# Power.net
KiCad netlist of a schematic drawn in Altium Designer
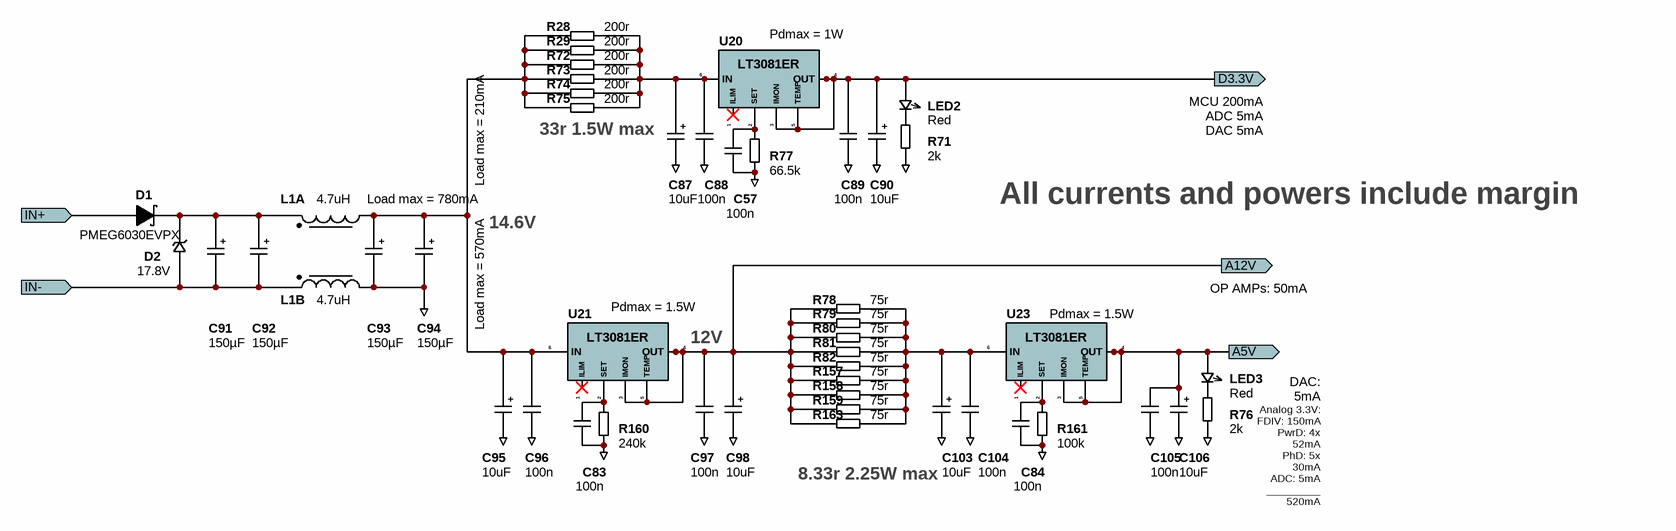
[diagram p0: Power.SchDoc]

(export (version "E")
  (design (tool "Eeschema 10.0.6"))
  (components
    (comp (ref "C57")
      (value "100n")
      (footprint "0402-Capacitor")
      (description "Capacitor 0402")
      (fields (field (name "TOLERANCE") "±20%"))
      (libsource (lib "PRL_PDC") (part "C_0402"))
    )
    (comp (ref "C83")
      (value "100n")
      (footprint "0402-Capacitor")
      (description "Capacitor 0402")
      (fields (field (name "TOLERANCE") "±20%"))
      (libsource (lib "PRL_PDC") (part "C_0402"))
    )
    (comp (ref "C84")
      (value "100n")
      (footprint "0402-Capacitor")
      (description "Capacitor 0402")
      (fields (field (name "TOLERANCE") "±20%"))
      (libsource (lib "PRL_PDC") (part "C_0402"))
    )
    (comp (ref "C87")
      (value "10uF")
      (footprint "2312-6032 Tantalum Capacitor")
      (description "CAP TANT 10UF 10% 25V 2312")
      (libsource (lib "PRL_PDC") (part "C_10uF_Tant_25V_2312"))
    )
    (comp (ref "C88")
      (value "100n")
      (footprint "0402-Capacitor")
      (description "Capacitor 0402")
      (fields (field (name "TOLERANCE") "±20%"))
      (libsource (lib "PRL_PDC") (part "C_0402"))
    )
    (comp (ref "C89")
      (value "100n")
      (footprint "0402-Capacitor")
      (description "Capacitor 0402")
      (fields (field (name "TOLERANCE") "±20%"))
      (libsource (lib "PRL_PDC") (part "C_0402"))
    )
    (comp (ref "C90")
      (value "10uF")
      (footprint "2312-6032 Tantalum Capacitor")
      (description "CAP TANT 10UF 10% 25V 2312")
      (libsource (lib "PRL_PDC") (part "C_10uF_Tant_25V_2312"))
    )
    (comp (ref "C91")
      (value "150µF")
      (footprint "2917-7343  Tantalum Capacitor")
      (description "150µF Molded Tantalum Capacitors 20V 2917")
      (fields (field (name "TOLERANCE") "±10%"))
      (libsource (lib "PRL_PDC") (part "T491X157K020AT"))
    )
    (comp (ref "C92")
      (value "150µF")
      (footprint "2917-7343  Tantalum Capacitor")
      (description "150µF Molded Tantalum Capacitors 20V 2917")
      (fields (field (name "TOLERANCE") "±10%"))
      (libsource (lib "PRL_PDC") (part "T491X157K020AT"))
    )
    (comp (ref "C93")
      (value "150µF")
      (footprint "2917-7343  Tantalum Capacitor")
      (description "150µF Molded Tantalum Capacitors 20V 2917")
      (fields (field (name "TOLERANCE") "±10%"))
      (libsource (lib "PRL_PDC") (part "T491X157K020AT"))
    )
    (comp (ref "C94")
      (value "150µF")
      (footprint "2917-7343  Tantalum Capacitor")
      (description "150µF Molded Tantalum Capacitors 20V 2917")
      (fields (field (name "TOLERANCE") "±10%"))
      (libsource (lib "PRL_PDC") (part "T491X157K020AT"))
    )
    (comp (ref "C95")
      (value "10uF")
      (footprint "2312-6032 Tantalum Capacitor")
      (description "CAP TANT 10UF 10% 25V 2312")
      (libsource (lib "PRL_PDC") (part "C_10uF_Tant_25V_2312"))
    )
    (comp (ref "C96")
      (value "100n")
      (footprint "0402-Capacitor")
      (description "Capacitor 0402")
      (fields (field (name "TOLERANCE") "±20%"))
      (libsource (lib "PRL_PDC") (part "C_0402"))
    )
    (comp (ref "C97")
      (value "100n")
      (footprint "0402-Capacitor")
      (description "Capacitor 0402")
      (fields (field (name "TOLERANCE") "±20%"))
      (libsource (lib "PRL_PDC") (part "C_0402"))
    )
    (comp (ref "C98")
      (value "10uF")
      (footprint "2312-6032 Tantalum Capacitor")
      (description "CAP TANT 10UF 10% 25V 2312")
      (libsource (lib "PRL_PDC") (part "C_10uF_Tant_25V_2312"))
    )
    (comp (ref "C103")
      (value "10uF")
      (footprint "2312-6032 Tantalum Capacitor")
      (description "CAP TANT 10UF 10% 25V 2312")
      (libsource (lib "PRL_PDC") (part "C_10uF_Tant_25V_2312"))
    )
    (comp (ref "C104")
      (value "100n")
      (footprint "0402-Capacitor")
      (description "Capacitor 0402")
      (fields (field (name "TOLERANCE") "±20%"))
      (libsource (lib "PRL_PDC") (part "C_0402"))
    )
    (comp (ref "C105")
      (value "100n")
      (footprint "0402-Capacitor")
      (description "Capacitor 0402")
      (fields (field (name "TOLERANCE") "±20%"))
      (libsource (lib "PRL_PDC") (part "C_0402"))
    )
    (comp (ref "C106")
      (value "10uF")
      (footprint "2312-6032 Tantalum Capacitor")
      (description "CAP TANT 10UF 10% 25V 2312")
      (libsource (lib "PRL_PDC") (part "C_10uF_Tant_25V_2312"))
    )
    (comp (ref "D1")
      (value "PMEG6030EVPX")
      (footprint "SOD128")
      (description "Diode Schottky 60V 3A Surface Mount SOD-128/CFP5")
      (fields (field (name "MANUFACTURER") "Nexperia USA Inc."))
      (libsource (lib "PRL_PDC") (part "PMEG6030EVPX"))
    )
    (comp (ref "D2")
      (value "17.8V")
      (footprint "DO-219AB")
      (description "26V Clamp 7.7A Ipp Tvs Diode Surface Mount SMF")
      (libsource (lib "PRL_PDC") (part "SMF16A-E3-08"))
    )
    (comp (ref "L1")
      (value "4.7uH")
      (footprint "PRL_PDC:LPD5030")
      (description "Shielded Coupled Inductor")
      (fields (field (name "TOLERANCE") "20%"))
      (libsource (lib "PRL_PDC") (part "LPD5030"))
    )
    (comp (ref "LED2") (value "Red") (footprint "LED0603") (libsource (lib "PRL_PDC") (part "LED0603")))
    (comp (ref "LED3") (value "Red") (footprint "LED0603") (libsource (lib "PRL_PDC") (part "LED0603")))
    (comp (ref "R28")
      (value "200r")
      (footprint "1210-Resistor")
      (description "Resistor 1210")
      (fields (field (name "TOLERANCE") "±1%"))
      (libsource (lib "PRL_PDC") (part "R_1210"))
    )
    (comp (ref "R29")
      (value "200r")
      (footprint "1210-Resistor")
      (description "Resistor 1210")
      (fields (field (name "TOLERANCE") "±1%"))
      (libsource (lib "PRL_PDC") (part "R_1210"))
    )
    (comp (ref "R71")
      (value "2k")
      (footprint "0402-RESISTOR")
      (description "Resistor 0402")
      (fields (field (name "TOLERANCE") "±1%"))
      (libsource (lib "PRL_PDC") (part "R_0402"))
    )
    (comp (ref "R72")
      (value "200r")
      (footprint "1210-Resistor")
      (description "Resistor 1210")
      (fields (field (name "TOLERANCE") "±1%"))
      (libsource (lib "PRL_PDC") (part "R_1210"))
    )
    (comp (ref "R73")
      (value "200r")
      (footprint "1210-Resistor")
      (description "Resistor 1210")
      (fields (field (name "TOLERANCE") "±1%"))
      (libsource (lib "PRL_PDC") (part "R_1210"))
    )
    (comp (ref "R74")
      (value "200r")
      (footprint "1210-Resistor")
      (description "Resistor 1210")
      (fields (field (name "TOLERANCE") "±1%"))
      (libsource (lib "PRL_PDC") (part "R_1210"))
    )
    (comp (ref "R75")
      (value "200r")
      (footprint "1210-Resistor")
      (description "Resistor 1210")
      (fields (field (name "TOLERANCE") "±1%"))
      (libsource (lib "PRL_PDC") (part "R_1210"))
    )
    (comp (ref "R76")
      (value "2k")
      (footprint "0402-RESISTOR")
      (description "Resistor 0402")
      (fields (field (name "TOLERANCE") "±1%"))
      (libsource (lib "PRL_PDC") (part "R_0402"))
    )
    (comp (ref "R77")
      (value "66.5k")
      (footprint "0805-Resistor")
      (description "Resistor 0805")
      (fields (field (name "TOLERANCE") "±1%"))
      (libsource (lib "PRL_PDC") (part "R_0805"))
    )
    (comp (ref "R78")
      (value "75r")
      (footprint "1210-Resistor")
      (description "Resistor 1210")
      (fields (field (name "TOLERANCE") "±1%"))
      (libsource (lib "PRL_PDC") (part "R_1210"))
    )
    (comp (ref "R79")
      (value "75r")
      (footprint "1210-Resistor")
      (description "Resistor 1210")
      (fields (field (name "TOLERANCE") "±1%"))
      (libsource (lib "PRL_PDC") (part "R_1210"))
    )
    (comp (ref "R80")
      (value "75r")
      (footprint "1210-Resistor")
      (description "Resistor 1210")
      (fields (field (name "TOLERANCE") "±1%"))
      (libsource (lib "PRL_PDC") (part "R_1210"))
    )
    (comp (ref "R81")
      (value "75r")
      (footprint "1210-Resistor")
      (description "Resistor 1210")
      (fields (field (name "TOLERANCE") "±1%"))
      (libsource (lib "PRL_PDC") (part "R_1210"))
    )
    (comp (ref "R82")
      (value "75r")
      (footprint "1210-Resistor")
      (description "Resistor 1210")
      (fields (field (name "TOLERANCE") "±1%"))
      (libsource (lib "PRL_PDC") (part "R_1210"))
    )
    (comp (ref "R157")
      (value "75r")
      (footprint "1210-Resistor")
      (description "Resistor 1210")
      (fields (field (name "TOLERANCE") "±1%"))
      (libsource (lib "PRL_PDC") (part "R_1210"))
    )
    (comp (ref "R158")
      (value "75r")
      (footprint "1210-Resistor")
      (description "Resistor 1210")
      (fields (field (name "TOLERANCE") "±1%"))
      (libsource (lib "PRL_PDC") (part "R_1210"))
    )
    (comp (ref "R159")
      (value "75r")
      (footprint "1210-Resistor")
      (description "Resistor 1210")
      (fields (field (name "TOLERANCE") "±1%"))
      (libsource (lib "PRL_PDC") (part "R_1210"))
    )
    (comp (ref "R160")
      (value "240k")
      (footprint "0805-Resistor")
      (description "Resistor 0805")
      (fields (field (name "TOLERANCE") "±1%"))
      (libsource (lib "PRL_PDC") (part "R_0805"))
    )
    (comp (ref "R161")
      (value "100k")
      (footprint "0805-Resistor")
      (description "Resistor 0805")
      (fields (field (name "TOLERANCE") "±1%"))
      (libsource (lib "PRL_PDC") (part "R_0805"))
    )
    (comp (ref "R163")
      (value "75r")
      (footprint "1210-Resistor")
      (description "Resistor 1210")
      (fields (field (name "TOLERANCE") "±1%"))
      (libsource (lib "PRL_PDC") (part "R_1210"))
    )
    (comp (ref "U20")
      (value "ADJ")
      (footprint "D2PAK7")
      (description "1.5A Single Resistor\r\nRugged Linear Regulator\r\nwith Monitors")
      (libsource (lib "PRL_PDC") (part "LT3081ER"))
    )
    (comp (ref "U21")
      (value "ADJ")
      (footprint "D2PAK7")
      (description "1.5A Single Resistor\r\nRugged Linear Regulator\r\nwith Monitors")
      (libsource (lib "PRL_PDC") (part "LT3081ER"))
    )
    (comp (ref "U23")
      (value "ADJ")
      (footprint "D2PAK7")
      (description "1.5A Single Resistor\r\nRugged Linear Regulator\r\nwith Monitors")
      (libsource (lib "PRL_PDC") (part "LT3081ER"))
    )
  )
  (nets
    (net (code "1") (name "/A5V") (class "Default")
      (node (ref "C105") (pin "2") (pinfunction "2_2") (pintype "passive"))
      (node (ref "C106") (pin "+") (pinfunction "+_+") (pintype "passive"))
      (node (ref "LED3") (pin "A") (pinfunction "A_A") (pintype "passive"))
      (node (ref "U23") (pin "3") (pinfunction "IMON_3") (pintype "passive"))
      (node (ref "U23") (pin "4") (pinfunction "OUT_4") (pintype "passive"))
      (node (ref "U23") (pin "5") (pinfunction "TEMP_5") (pintype "passive"))
      (node (ref "U23") (pin "EP") (pinfunction "OUT_EP") (pintype "passive"))
    )
    (net (code "2") (name "/A12V") (class "Default")
      (node (ref "C97") (pin "2") (pinfunction "2_2") (pintype "passive"))
      (node (ref "C98") (pin "+") (pinfunction "+_+") (pintype "passive"))
      (node (ref "R157") (pin "1") (pinfunction "1_1") (pintype "passive"))
      (node (ref "R158") (pin "1") (pinfunction "1_1") (pintype "passive"))
      (node (ref "R159") (pin "1") (pinfunction "1_1") (pintype "passive"))
      (node (ref "R163") (pin "1") (pinfunction "1_1") (pintype "passive"))
      (node (ref "R78") (pin "1") (pinfunction "1_1") (pintype "passive"))
      (node (ref "R79") (pin "1") (pinfunction "1_1") (pintype "passive"))
      (node (ref "R80") (pin "1") (pinfunction "1_1") (pintype "passive"))
      (node (ref "R81") (pin "1") (pinfunction "1_1") (pintype "passive"))
      (node (ref "R82") (pin "1") (pinfunction "1_1") (pintype "passive"))
      (node (ref "U21") (pin "3") (pinfunction "IMON_3") (pintype "passive"))
      (node (ref "U21") (pin "4") (pinfunction "OUT_4") (pintype "passive"))
      (node (ref "U21") (pin "5") (pinfunction "TEMP_5") (pintype "passive"))
      (node (ref "U21") (pin "EP") (pinfunction "OUT_EP") (pintype "passive"))
    )
    (net (code "3") (name "/D3.3V") (class "Default")
      (node (ref "C89") (pin "2") (pinfunction "2_2") (pintype "passive"))
      (node (ref "C90") (pin "+") (pinfunction "+_+") (pintype "passive"))
      (node (ref "LED2") (pin "A") (pinfunction "A_A") (pintype "passive"))
      (node (ref "U20") (pin "3") (pinfunction "IMON_3") (pintype "passive"))
      (node (ref "U20") (pin "4") (pinfunction "OUT_4") (pintype "passive"))
      (node (ref "U20") (pin "5") (pinfunction "TEMP_5") (pintype "passive"))
      (node (ref "U20") (pin "EP") (pinfunction "OUT_EP") (pintype "passive"))
    )
    (net (code "4") (name "/IN+") (class "Default")
      (node (ref "D1") (pin "1") (pinfunction "A_1") (pintype "passive"))
    )
    (net (code "5") (name "/IN-") (class "Default")
      (node (ref "C91") (pin "-") (pinfunction "-_-") (pintype "passive"))
      (node (ref "C92") (pin "-") (pinfunction "-_-") (pintype "passive"))
      (node (ref "D2") (pin "A") (pinfunction "A_A") (pintype "passive"))
      (node (ref "L1") (pin "4") (pinfunction "4_4") (pintype "passive"))
    )
    (net (code "6") (name "GND") (class "Default")
      (node (ref "C103") (pin "-") (pinfunction "-_-") (pintype "passive"))
      (node (ref "C104") (pin "1") (pinfunction "1_1") (pintype "passive"))
      (node (ref "C105") (pin "1") (pinfunction "1_1") (pintype "passive"))
      (node (ref "C106") (pin "-") (pinfunction "-_-") (pintype "passive"))
      (node (ref "C57") (pin "1") (pinfunction "1_1") (pintype "passive"))
      (node (ref "C83") (pin "1") (pinfunction "1_1") (pintype "passive"))
      (node (ref "C84") (pin "1") (pinfunction "1_1") (pintype "passive"))
      (node (ref "C87") (pin "-") (pinfunction "-_-") (pintype "passive"))
      (node (ref "C88") (pin "1") (pinfunction "1_1") (pintype "passive"))
      (node (ref "C89") (pin "1") (pinfunction "1_1") (pintype "passive"))
      (node (ref "C90") (pin "-") (pinfunction "-_-") (pintype "passive"))
      (node (ref "C93") (pin "-") (pinfunction "-_-") (pintype "passive"))
      (node (ref "C94") (pin "-") (pinfunction "-_-") (pintype "passive"))
      (node (ref "C95") (pin "-") (pinfunction "-_-") (pintype "passive"))
      (node (ref "C96") (pin "1") (pinfunction "1_1") (pintype "passive"))
      (node (ref "C97") (pin "1") (pinfunction "1_1") (pintype "passive"))
      (node (ref "C98") (pin "-") (pinfunction "-_-") (pintype "passive"))
      (node (ref "L1") (pin "3") (pinfunction "3_3") (pintype "passive"))
      (node (ref "R160") (pin "1") (pinfunction "1_1") (pintype "passive"))
      (node (ref "R161") (pin "1") (pinfunction "1_1") (pintype "passive"))
      (node (ref "R71") (pin "1") (pinfunction "1_1") (pintype "passive"))
      (node (ref "R76") (pin "1") (pinfunction "1_1") (pintype "passive"))
      (node (ref "R77") (pin "1") (pinfunction "1_1") (pintype "passive"))
    )
    (net (code "7") (name "Net-(D1-K)") (class "Default")
      (node (ref "C91") (pin "+") (pinfunction "+_+") (pintype "passive"))
      (node (ref "C92") (pin "+") (pinfunction "+_+") (pintype "passive"))
      (node (ref "D1") (pin "2") (pinfunction "K_2") (pintype "passive"))
      (node (ref "D2") (pin "K") (pinfunction "K_K") (pintype "passive"))
      (node (ref "L1") (pin "1") (pinfunction "1_1") (pintype "passive"))
    )
    (net (code "8") (name "Net-(LED2-PadK)") (class "Default")
      (node (ref "LED2") (pin "K") (pinfunction "K_K") (pintype "passive"))
      (node (ref "R71") (pin "2") (pinfunction "2_2") (pintype "passive"))
    )
    (net (code "9") (name "Net-(LED3-PadK)") (class "Default")
      (node (ref "LED3") (pin "K") (pinfunction "K_K") (pintype "passive"))
      (node (ref "R76") (pin "2") (pinfunction "2_2") (pintype "passive"))
    )
    (net (code "10") (name "Net-(U20-IN)") (class "Default")
      (node (ref "C87") (pin "+") (pinfunction "+_+") (pintype "passive"))
      (node (ref "C88") (pin "2") (pinfunction "2_2") (pintype "passive"))
      (node (ref "R28") (pin "2") (pinfunction "2_2") (pintype "passive"))
      (node (ref "R29") (pin "2") (pinfunction "2_2") (pintype "passive"))
      (node (ref "R72") (pin "2") (pinfunction "2_2") (pintype "passive"))
      (node (ref "R73") (pin "2") (pinfunction "2_2") (pintype "passive"))
      (node (ref "R74") (pin "2") (pinfunction "2_2") (pintype "passive"))
      (node (ref "R75") (pin "2") (pinfunction "2_2") (pintype "passive"))
      (node (ref "U20") (pin "6") (pinfunction "IN_6") (pintype "passive"))
    )
    (net (code "11") (name "Net-(U20-SET)") (class "Default")
      (node (ref "C57") (pin "2") (pinfunction "2_2") (pintype "passive"))
      (node (ref "R77") (pin "2") (pinfunction "2_2") (pintype "passive"))
      (node (ref "U20") (pin "2") (pinfunction "SET_2") (pintype "passive"))
    )
    (net (code "12") (name "Net-(U21-IN)") (class "Default")
      (node (ref "C93") (pin "+") (pinfunction "+_+") (pintype "passive"))
      (node (ref "C94") (pin "+") (pinfunction "+_+") (pintype "passive"))
      (node (ref "C95") (pin "+") (pinfunction "+_+") (pintype "passive"))
      (node (ref "C96") (pin "2") (pinfunction "2_2") (pintype "passive"))
      (node (ref "L1") (pin "2") (pinfunction "2_2") (pintype "passive"))
      (node (ref "R28") (pin "1") (pinfunction "1_1") (pintype "passive"))
      (node (ref "R29") (pin "1") (pinfunction "1_1") (pintype "passive"))
      (node (ref "R72") (pin "1") (pinfunction "1_1") (pintype "passive"))
      (node (ref "R73") (pin "1") (pinfunction "1_1") (pintype "passive"))
      (node (ref "R74") (pin "1") (pinfunction "1_1") (pintype "passive"))
      (node (ref "R75") (pin "1") (pinfunction "1_1") (pintype "passive"))
      (node (ref "U21") (pin "6") (pinfunction "IN_6") (pintype "passive"))
    )
    (net (code "13") (name "Net-(U21-SET)") (class "Default")
      (node (ref "C83") (pin "2") (pinfunction "2_2") (pintype "passive"))
      (node (ref "R160") (pin "2") (pinfunction "2_2") (pintype "passive"))
      (node (ref "U21") (pin "2") (pinfunction "SET_2") (pintype "passive"))
    )
    (net (code "14") (name "Net-(U23-IN)") (class "Default")
      (node (ref "C103") (pin "+") (pinfunction "+_+") (pintype "passive"))
      (node (ref "C104") (pin "2") (pinfunction "2_2") (pintype "passive"))
      (node (ref "R157") (pin "2") (pinfunction "2_2") (pintype "passive"))
      (node (ref "R158") (pin "2") (pinfunction "2_2") (pintype "passive"))
      (node (ref "R159") (pin "2") (pinfunction "2_2") (pintype "passive"))
      (node (ref "R163") (pin "2") (pinfunction "2_2") (pintype "passive"))
      (node (ref "R78") (pin "2") (pinfunction "2_2") (pintype "passive"))
      (node (ref "R79") (pin "2") (pinfunction "2_2") (pintype "passive"))
      (node (ref "R80") (pin "2") (pinfunction "2_2") (pintype "passive"))
      (node (ref "R81") (pin "2") (pinfunction "2_2") (pintype "passive"))
      (node (ref "R82") (pin "2") (pinfunction "2_2") (pintype "passive"))
      (node (ref "U23") (pin "6") (pinfunction "IN_6") (pintype "passive"))
    )
    (net (code "15") (name "Net-(U23-SET)") (class "Default")
      (node (ref "C84") (pin "2") (pinfunction "2_2") (pintype "passive"))
      (node (ref "R161") (pin "2") (pinfunction "2_2") (pintype "passive"))
      (node (ref "U23") (pin "2") (pinfunction "SET_2") (pintype "passive"))
    )
    (net (code "16") (name "unconnected-(U20-ILIM-Pad1)") (class "Default")
      (node (ref "U20") (pin "1") (pinfunction "ILIM_1") (pintype "passive+no_connect"))
    )
    (net (code "17") (name "unconnected-(U20-NC-Pad7)") (class "Default")
      (node (ref "U20") (pin "7") (pinfunction "NC_7") (pintype "passive"))
    )
    (net (code "18") (name "unconnected-(U21-ILIM-Pad1)") (class "Default")
      (node (ref "U21") (pin "1") (pinfunction "ILIM_1") (pintype "passive+no_connect"))
    )
    (net (code "19") (name "unconnected-(U21-NC-Pad7)") (class "Default")
      (node (ref "U21") (pin "7") (pinfunction "NC_7") (pintype "passive"))
    )
    (net (code "20") (name "unconnected-(U23-ILIM-Pad1)") (class "Default")
      (node (ref "U23") (pin "1") (pinfunction "ILIM_1") (pintype "passive+no_connect"))
    )
    (net (code "21") (name "unconnected-(U23-NC-Pad7)") (class "Default")
      (node (ref "U23") (pin "7") (pinfunction "NC_7") (pintype "passive"))
    )
  )
)
